# IR_Schreib_Lesekopf_RS232_Neu.net
KiCad netlist of a schematic drawn in EAGLE
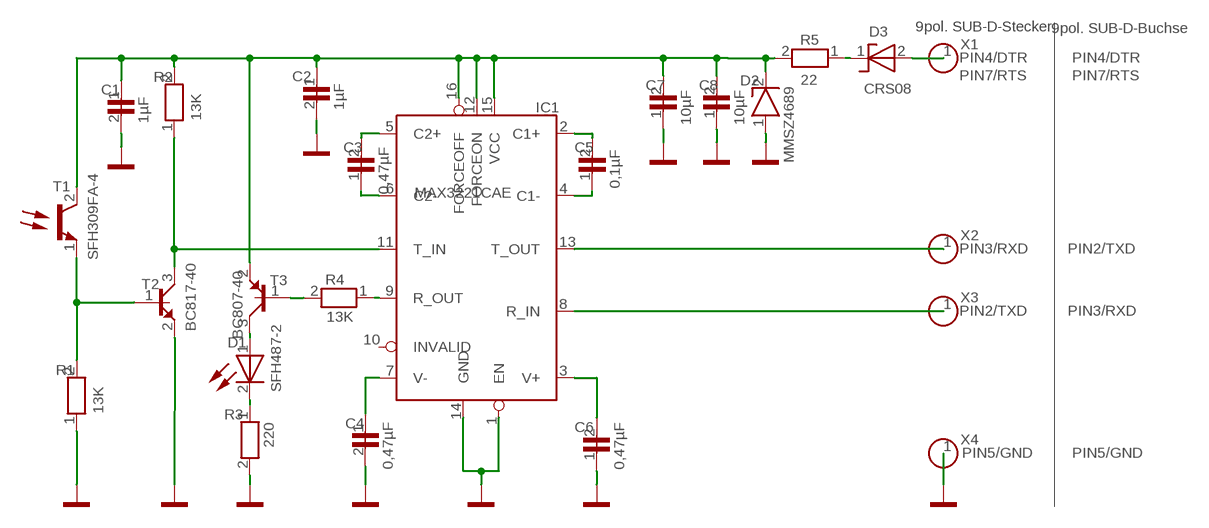
[diagram p0: schematic, sheet 1]

(export (version "E")
  (design (tool "Eeschema 10.0.6"))
  (components
    (comp (ref "C1")
      (value "1µF")
      (footprint "eagle-import:0603_KLEIN_25")
      (libsource (lib "eagle-import") (part "C_KERAMIK_0,1µF_0805_25"))
    )
    (comp (ref "C2")
      (value "1µF")
      (footprint "eagle-import:1206_29")
      (libsource (lib "eagle-import") (part "C_KERAMIK_0,1µF_0805_29"))
    )
    (comp (ref "C3")
      (value "0,47µF")
      (footprint "eagle-import:0603_13")
      (libsource (lib "eagle-import") (part "223858615609_13"))
    )
    (comp (ref "C4")
      (value "0,47µF")
      (footprint "eagle-import:0603_0")
      (libsource (lib "eagle-import") (part "223858615609_0"))
    )
    (comp (ref "C5")
      (value "0,1µF")
      (footprint "eagle-import:0603_12")
      (libsource (lib "eagle-import") (part "223858615609_12"))
    )
    (comp (ref "C6")
      (value "0,47µF")
      (footprint "eagle-import:0603_1")
      (libsource (lib "eagle-import") (part "223858615609_1"))
    )
    (comp (ref "C7")
      (value "10µF")
      (footprint "eagle-import:0805_KLEIN_34")
      (libsource (lib "eagle-import") (part "223858615609_34"))
    )
    (comp (ref "C8")
      (value "10µF")
      (footprint "eagle-import:0805_KLEIN_2")
      (libsource (lib "eagle-import") (part "223858615609_2"))
    )
    (comp (ref "D1")
      (value "SFH487-2")
      (footprint "eagle-import:LED_3MM_26")
      (libsource (lib "eagle-import") (part "CN304_26"))
    )
    (comp (ref "D2")
      (value "MMSZ4689")
      (footprint "eagle-import:DO214AA_15")
      (libsource (lib "eagle-import") (part "BZG03C_15"))
    )
    (comp (ref "D3")
      (value "CRS08")
      (footprint "eagle-import:SOD123_17")
      (libsource (lib "eagle-import") (part "BAT46W_17"))
    )
    (comp (ref "IC1")
      (value "MAX3221CAE")
      (footprint "eagle-import:SSOP16_11")
      (libsource (lib "eagle-import") (part "MAX3221CAE_11"))
    )
    (comp (ref "R1")
      (value "13K")
      (footprint "eagle-import:0603_KLEIN_20")
      (libsource (lib "eagle-import") (part "R-0805_20"))
    )
    (comp (ref "R2")
      (value "13K")
      (footprint "eagle-import:0603_KLEIN_21")
      (libsource (lib "eagle-import") (part "R-0805_21"))
    )
    (comp (ref "R3")
      (value "220")
      (footprint "eagle-import:0603_KLEIN_31")
      (libsource (lib "eagle-import") (part "R-0805_31"))
    )
    (comp (ref "R4")
      (value "13K")
      (footprint "eagle-import:0603_KLEIN_27")
      (libsource (lib "eagle-import") (part "R-0805_27"))
    )
    (comp (ref "R5")
      (value "22")
      (footprint "eagle-import:1206_18")
      (libsource (lib "eagle-import") (part "R-1206_18"))
    )
    (comp (ref "T1")
      (value "SFH309FA-4")
      (footprint "eagle-import:FOTO_4MM_19")
      (libsource (lib "eagle-import") (part "SFH309-4_19"))
    )
    (comp (ref "T2")
      (value "BC817-40")
      (footprint "eagle-import:SOT23_3_33")
      (libsource (lib "eagle-import") (part "BC817-40_33"))
    )
    (comp (ref "T3")
      (value "BC807-40")
      (footprint "eagle-import:SOT23_3_32")
      (libsource (lib "eagle-import") (part "BC807-40_32"))
    )
    (comp (ref "X1")
      (value "PIN4/DTR")
      (footprint "eagle-import:LOETPUNKT_7")
      (libsource (lib "eagle-import") (part "LOETPUNKT_7"))
    )
    (comp (ref "X2")
      (value "PIN3/RXD")
      (footprint "eagle-import:LOETPUNKT_9")
      (libsource (lib "eagle-import") (part "LOETPUNKT_9"))
    )
    (comp (ref "X3")
      (value "PIN2/TXD")
      (footprint "eagle-import:LOETPUNKT_8")
      (libsource (lib "eagle-import") (part "LOETPUNKT_8"))
    )
    (comp (ref "X4")
      (value "PIN5/GND")
      (footprint "eagle-import:LOETPUNKT_10")
      (libsource (lib "eagle-import") (part "LOETPUNKT_10"))
    )
  )
  (nets
    (net (code "1") (name "GND") (class "Default")
      (node (ref "C1") (pin "2") (pinfunction "2_2") (pintype "passive"))
      (node (ref "C2") (pin "2") (pinfunction "2_2") (pintype "passive"))
      (node (ref "C4") (pin "2") (pinfunction "2_2") (pintype "passive"))
      (node (ref "C6") (pin "1") (pinfunction "1_1") (pintype "passive"))
      (node (ref "C7") (pin "1") (pinfunction "1_1") (pintype "passive"))
      (node (ref "C8") (pin "1") (pinfunction "1_1") (pintype "passive"))
      (node (ref "D2") (pin "1") (pinfunction "1_1") (pintype "passive"))
      (node (ref "IC1") (pin "1") (pinfunction "EN_1") (pintype "input"))
      (node (ref "IC1") (pin "14") (pinfunction "GND_14") (pintype "power_in"))
      (node (ref "R1") (pin "1") (pinfunction "1_1") (pintype "passive"))
      (node (ref "R3") (pin "2") (pinfunction "2_2") (pintype "passive"))
      (node (ref "T2") (pin "2") (pinfunction "2_2") (pintype "passive"))
      (node (ref "X4") (pin "1") (pinfunction "1_1") (pintype "passive"))
    )
    (net (code "2") (name "Net-(D1-Pad1)") (class "Default")
      (node (ref "D1") (pin "1") (pinfunction "1_1") (pintype "passive"))
      (node (ref "T3") (pin "3") (pinfunction "3_3") (pintype "passive"))
    )
    (net (code "3") (name "Net-(D1-Pad2)") (class "Default")
      (node (ref "D1") (pin "2") (pinfunction "2_2") (pintype "passive"))
      (node (ref "R3") (pin "1") (pinfunction "1_1") (pintype "passive"))
    )
    (net (code "4") (name "Net-(D3-Pad1)") (class "Default")
      (node (ref "D3") (pin "1") (pinfunction "1_1") (pintype "passive"))
      (node (ref "R5") (pin "1") (pinfunction "1_1") (pintype "passive"))
    )
    (net (code "5") (name "Net-(D3-Pad2)") (class "Default")
      (node (ref "D3") (pin "2") (pinfunction "2_2") (pintype "passive"))
      (node (ref "X1") (pin "1") (pinfunction "1_1") (pintype "passive"))
    )
    (net (code "6") (name "Net-(IC1-C1+)") (class "Default")
      (node (ref "C5") (pin "2") (pinfunction "2_2") (pintype "passive"))
      (node (ref "IC1") (pin "2") (pinfunction "C1+_2") (pintype "passive"))
    )
    (net (code "7") (name "Net-(IC1-C1-)") (class "Default")
      (node (ref "C5") (pin "1") (pinfunction "1_1") (pintype "passive"))
      (node (ref "IC1") (pin "4") (pinfunction "C1-_4") (pintype "passive"))
    )
    (net (code "8") (name "Net-(IC1-C2+)") (class "Default")
      (node (ref "C3") (pin "2") (pinfunction "2_2") (pintype "passive"))
      (node (ref "IC1") (pin "5") (pinfunction "C2+_5") (pintype "passive"))
    )
    (net (code "9") (name "Net-(IC1-C2-)") (class "Default")
      (node (ref "C3") (pin "1") (pinfunction "1_1") (pintype "passive"))
      (node (ref "IC1") (pin "6") (pinfunction "C2-_6") (pintype "passive"))
    )
    (net (code "10") (name "Net-(IC1-FORCEOFF)") (class "Default")
      (node (ref "C1") (pin "1") (pinfunction "1_1") (pintype "passive"))
      (node (ref "C2") (pin "1") (pinfunction "1_1") (pintype "passive"))
      (node (ref "C7") (pin "2") (pinfunction "2_2") (pintype "passive"))
      (node (ref "C8") (pin "2") (pinfunction "2_2") (pintype "passive"))
      (node (ref "D2") (pin "2") (pinfunction "2_2") (pintype "passive"))
      (node (ref "IC1") (pin "12") (pinfunction "FORCEON_12") (pintype "passive"))
      (node (ref "IC1") (pin "15") (pinfunction "VCC_15") (pintype "power_in"))
      (node (ref "IC1") (pin "16") (pinfunction "FORCEOFF_16") (pintype "passive"))
      (node (ref "R2") (pin "2") (pinfunction "2_2") (pintype "passive"))
      (node (ref "R5") (pin "2") (pinfunction "2_2") (pintype "passive"))
      (node (ref "T1") (pin "2") (pinfunction "2_2") (pintype "passive"))
      (node (ref "T3") (pin "2") (pinfunction "2_2") (pintype "passive"))
    )
    (net (code "11") (name "Net-(IC1-R_IN)") (class "Default")
      (node (ref "IC1") (pin "8") (pinfunction "R_IN_8") (pintype "input"))
      (node (ref "X3") (pin "1") (pinfunction "1_1") (pintype "passive"))
    )
    (net (code "12") (name "Net-(IC1-R_OUT)") (class "Default")
      (node (ref "IC1") (pin "9") (pinfunction "R_OUT_9") (pintype "output"))
      (node (ref "R4") (pin "1") (pinfunction "1_1") (pintype "passive"))
    )
    (net (code "13") (name "Net-(IC1-T_IN)") (class "Default")
      (node (ref "IC1") (pin "11") (pinfunction "T_IN_11") (pintype "input"))
      (node (ref "R2") (pin "1") (pinfunction "1_1") (pintype "passive"))
      (node (ref "T2") (pin "3") (pinfunction "3_3") (pintype "passive"))
    )
    (net (code "14") (name "Net-(IC1-T_OUT)") (class "Default")
      (node (ref "IC1") (pin "13") (pinfunction "T_OUT_13") (pintype "output"))
      (node (ref "X2") (pin "1") (pinfunction "1_1") (pintype "passive"))
    )
    (net (code "15") (name "Net-(IC1-V+)") (class "Default")
      (node (ref "C6") (pin "2") (pinfunction "2_2") (pintype "passive"))
      (node (ref "IC1") (pin "3") (pinfunction "V+_3") (pintype "power_in"))
    )
    (net (code "16") (name "Net-(IC1-V-)") (class "Default")
      (node (ref "C4") (pin "1") (pinfunction "1_1") (pintype "passive"))
      (node (ref "IC1") (pin "7") (pinfunction "V-_7") (pintype "power_in"))
    )
    (net (code "17") (name "Net-(R1-Pad2)") (class "Default")
      (node (ref "R1") (pin "2") (pinfunction "2_2") (pintype "passive"))
      (node (ref "T1") (pin "1") (pinfunction "1_1") (pintype "passive"))
      (node (ref "T2") (pin "1") (pinfunction "1_1") (pintype "passive"))
    )
    (net (code "18") (name "Net-(R4-Pad2)") (class "Default")
      (node (ref "R4") (pin "2") (pinfunction "2_2") (pintype "passive"))
      (node (ref "T3") (pin "1") (pinfunction "1_1") (pintype "passive"))
    )
    (net (code "19") (name "unconnected-(IC1-INVALID-Pad10)") (class "Default")
      (node (ref "IC1") (pin "10") (pinfunction "INVALID_10") (pintype "output"))
    )
  )
)
